# Backplane.net
KiCad netlist of a schematic drawn in EAGLE
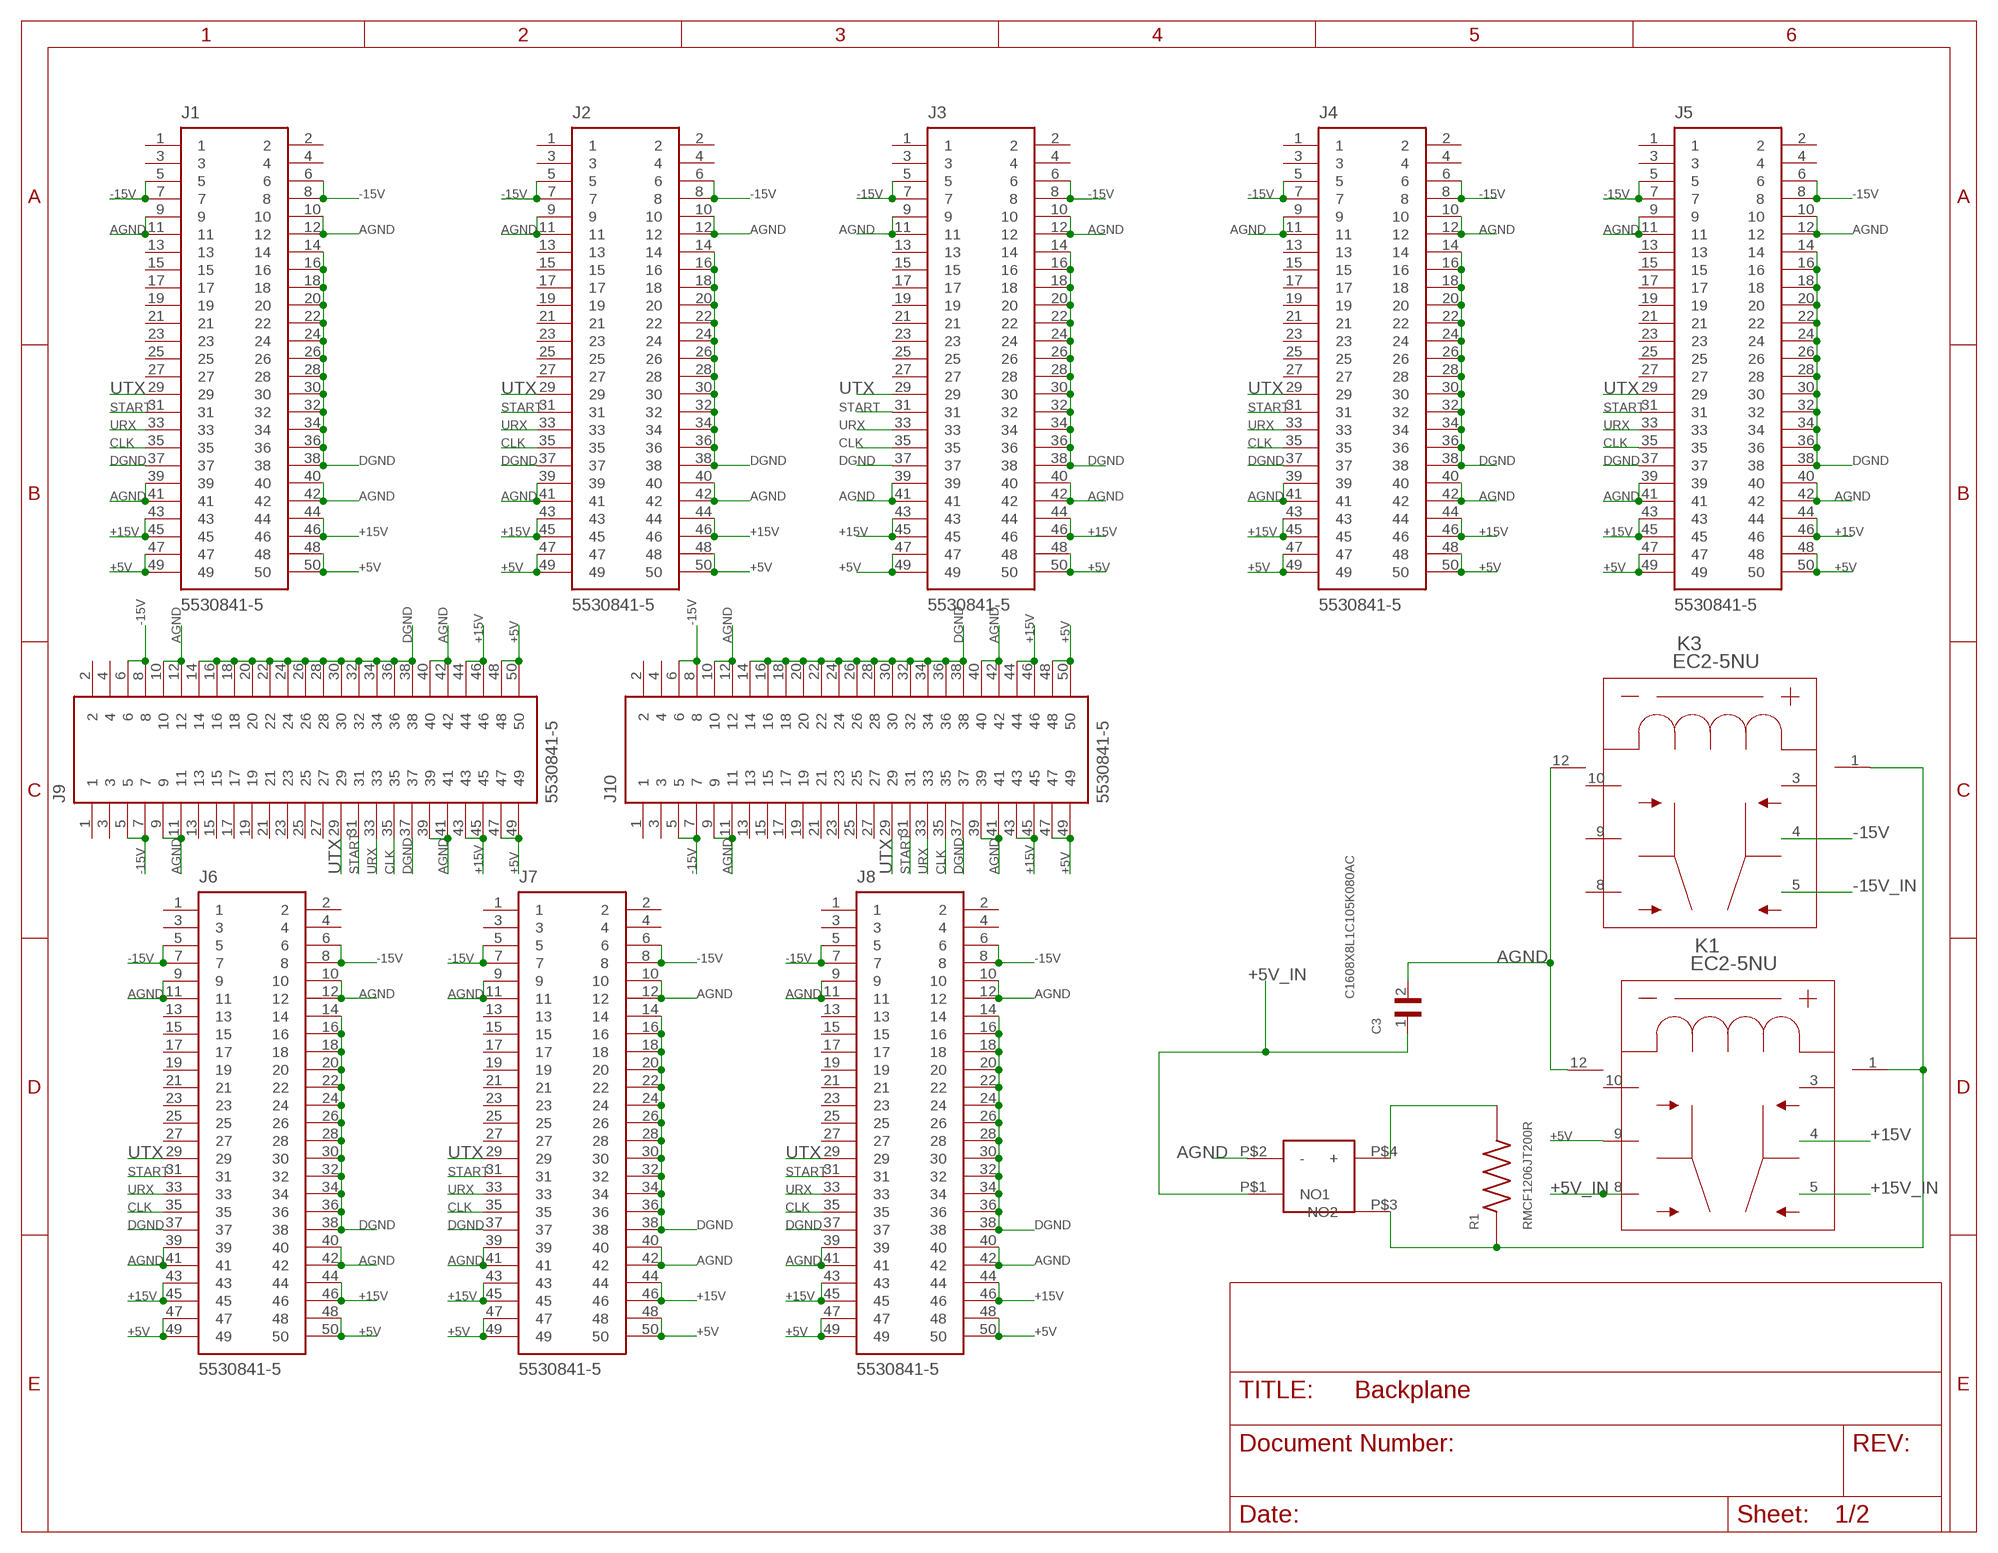
[diagram p0: schematic, sheet 1]
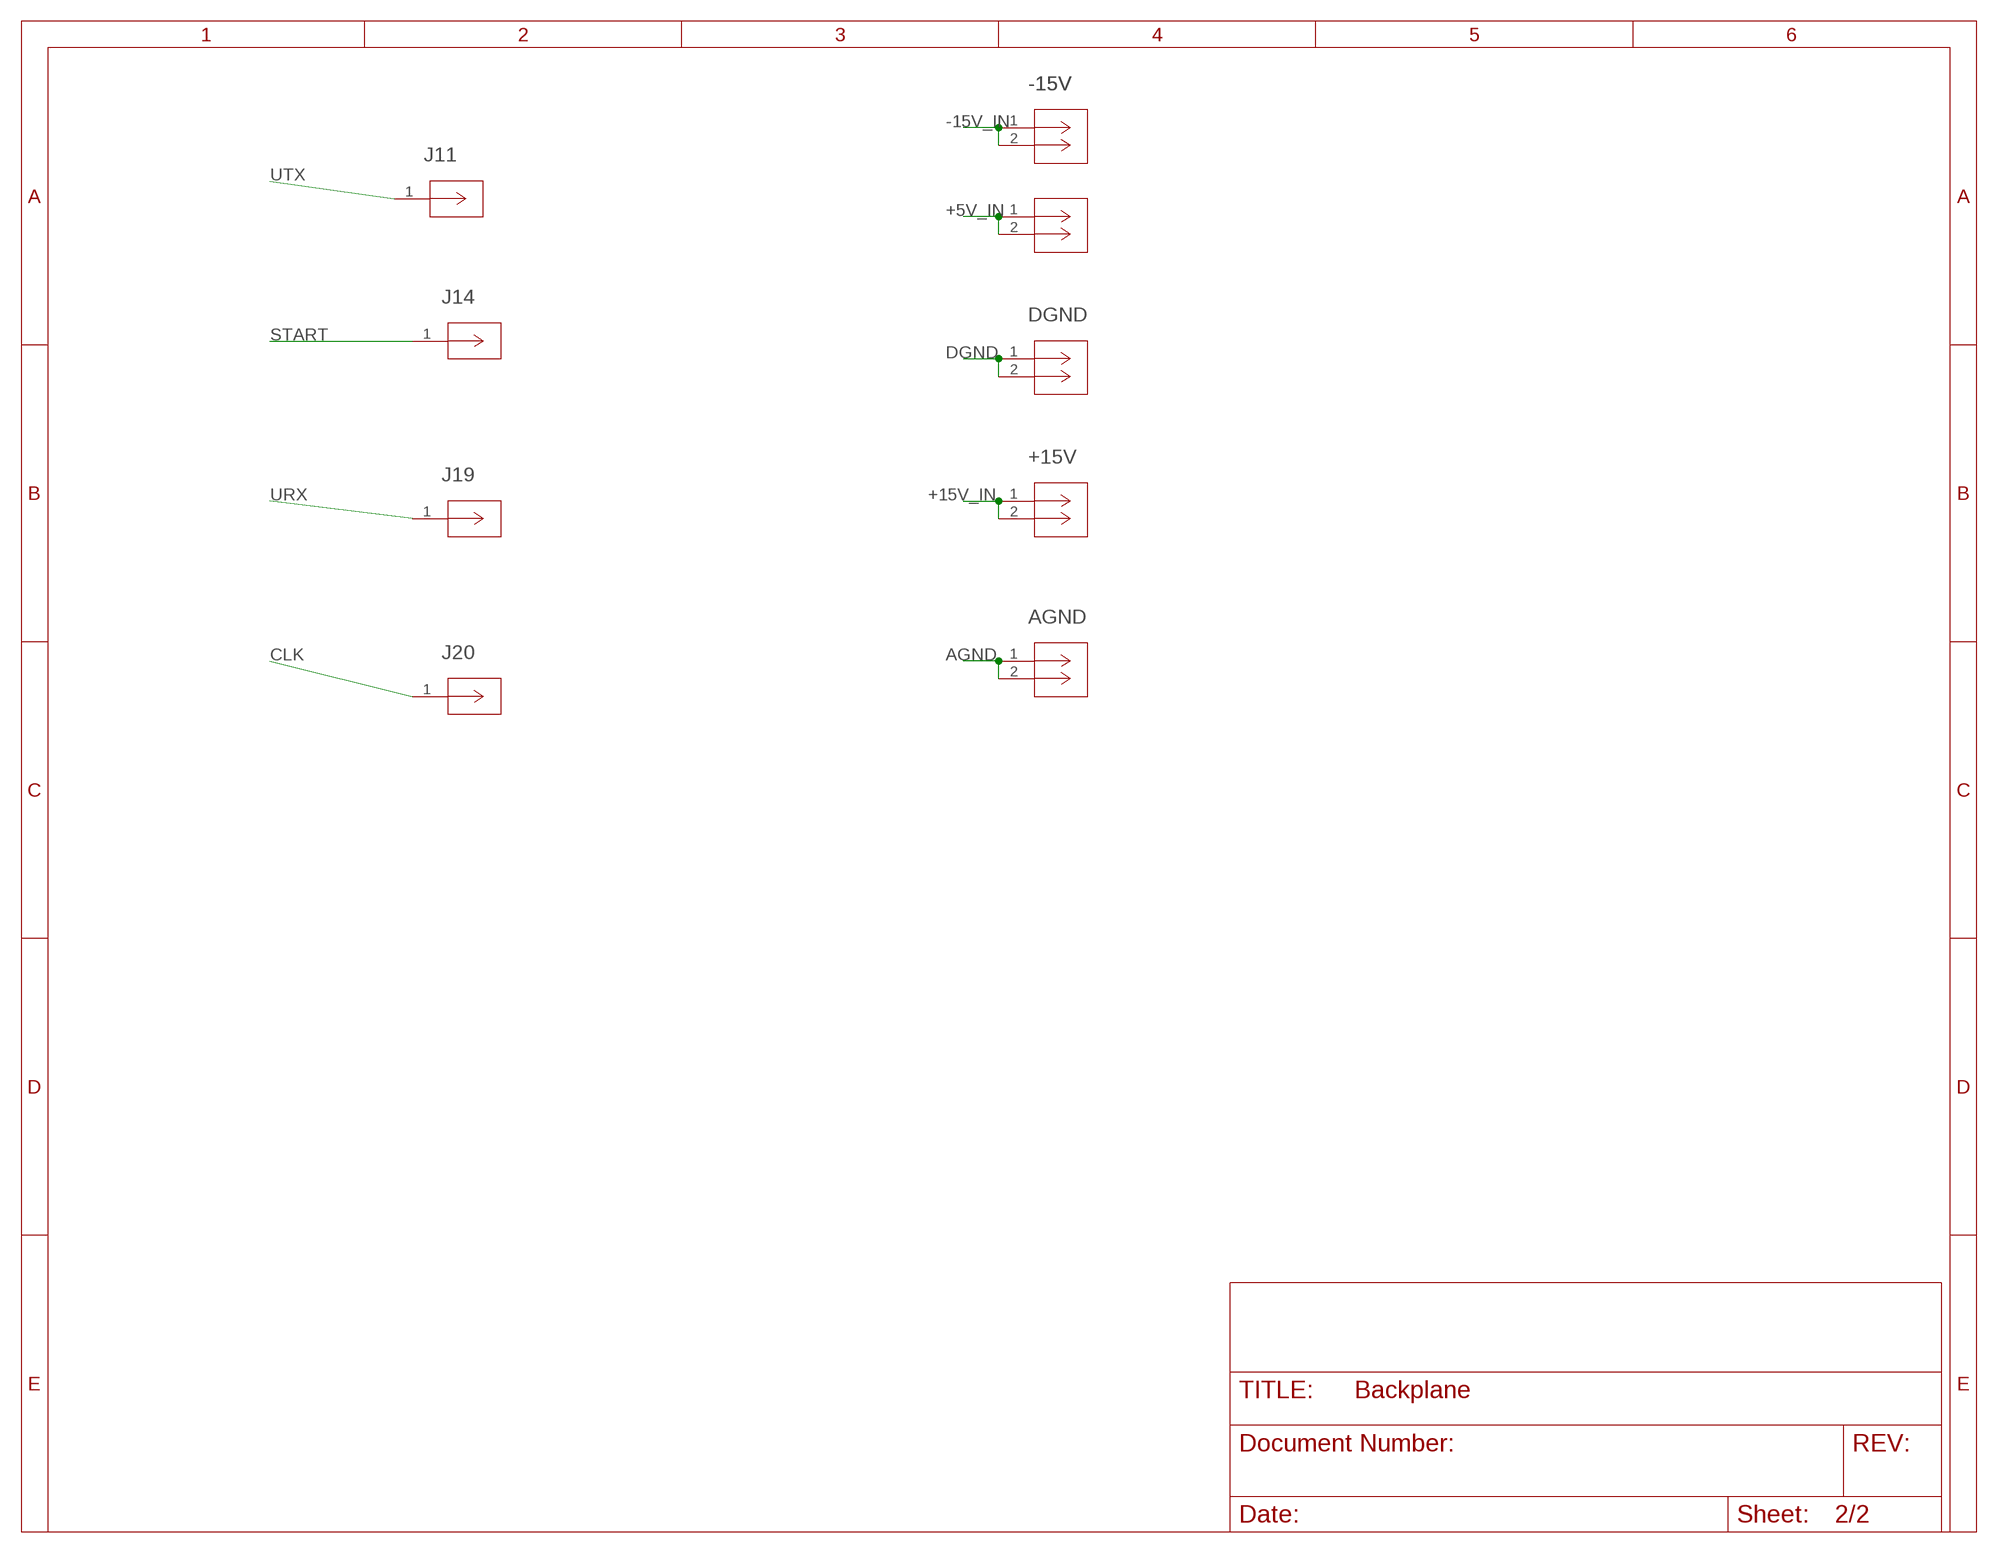
[diagram p1: schematic, sheet 2]

(export (version "E")
  (design (tool "Eeschema 10.0.6"))
  (components
    (comp (ref "C3")
      (value "C1608X8L1C105K080AC")
      (footprint "eagle-import:CAPC1608X90N")
      (fields (field (name "DIGI-KEY_PART_NUMBER") "445-175407-1-ND") (field (name "MF") "TDK"))
      (libsource (lib "eagle-import") (part "C1608X8L1C105K080AC"))
    )
    (comp (ref "J1")
      (value "5530841-5")
      (footprint "eagle-import:TE_5530841-5")
      (fields (field (name "DIGI-KEY_PART_NUMBER") "5530841-5-ND") (field (name "MF") "TE Connectivity"))
      (libsource (lib "eagle-import") (part "5530841-5"))
    )
    (comp (ref "J2")
      (value "5530841-5")
      (footprint "eagle-import:TE_5530841-5")
      (fields (field (name "DIGI-KEY_PART_NUMBER") "5530841-5-ND") (field (name "MF") "TE Connectivity"))
      (libsource (lib "eagle-import") (part "5530841-5"))
    )
    (comp (ref "J3")
      (value "5530841-5")
      (footprint "eagle-import:TE_5530841-5")
      (fields (field (name "DIGI-KEY_PART_NUMBER") "5530841-5-ND") (field (name "MF") "TE Connectivity"))
      (libsource (lib "eagle-import") (part "5530841-5"))
    )
    (comp (ref "J4")
      (value "5530841-5")
      (footprint "eagle-import:TE_5530841-5")
      (fields (field (name "DIGI-KEY_PART_NUMBER") "5530841-5-ND") (field (name "MF") "TE Connectivity"))
      (libsource (lib "eagle-import") (part "5530841-5"))
    )
    (comp (ref "J5")
      (value "5530841-5")
      (footprint "eagle-import:TE_5530841-5")
      (fields (field (name "DIGI-KEY_PART_NUMBER") "5530841-5-ND") (field (name "MF") "TE Connectivity"))
      (libsource (lib "eagle-import") (part "5530841-5"))
    )
    (comp (ref "J6")
      (value "5530841-5")
      (footprint "eagle-import:TE_5530841-5")
      (fields (field (name "DIGI-KEY_PART_NUMBER") "5530841-5-ND") (field (name "MF") "TE Connectivity"))
      (libsource (lib "eagle-import") (part "5530841-5"))
    )
    (comp (ref "J7")
      (value "5530841-5")
      (footprint "eagle-import:TE_5530841-5")
      (fields (field (name "DIGI-KEY_PART_NUMBER") "5530841-5-ND") (field (name "MF") "TE Connectivity"))
      (libsource (lib "eagle-import") (part "5530841-5"))
    )
    (comp (ref "J8")
      (value "5530841-5")
      (footprint "eagle-import:TE_5530841-5")
      (fields (field (name "DIGI-KEY_PART_NUMBER") "5530841-5-ND") (field (name "MF") "TE Connectivity"))
      (libsource (lib "eagle-import") (part "5530841-5"))
    )
    (comp (ref "J9")
      (value "5530841-5")
      (footprint "eagle-import:TE_5530841-5")
      (fields (field (name "DIGI-KEY_PART_NUMBER") "5530841-5-ND") (field (name "MF") "TE Connectivity"))
      (libsource (lib "eagle-import") (part "5530841-5"))
    )
    (comp (ref "J10")
      (value "5530841-5")
      (footprint "eagle-import:TE_5530841-5")
      (fields (field (name "DIGI-KEY_PART_NUMBER") "5530841-5-ND") (field (name "MF") "TE Connectivity"))
      (libsource (lib "eagle-import") (part "5530841-5"))
    )
    (comp (ref "K1")
      (value "EC2-5NU")
      (footprint "eagle-import:EC2NU")
      (fields (field (name "MANUFACTURER_PART_NUMBER") "EC25NU"))
      (libsource (lib "eagle-import") (part "EC2-5NU"))
    )
    (comp (ref "K3")
      (value "EC2-5NU")
      (footprint "eagle-import:EC2NU")
      (fields (field (name "MANUFACTURER_PART_NUMBER") "EC25NU"))
      (libsource (lib "eagle-import") (part "EC2-5NU"))
    )
    (comp (ref "R1")
      (value "RMCF1206JT200R")
      (footprint "eagle-import:RESC3216X70N")
      (fields
        (field (name "DIGI-KEY_PART_NUMBER") "RMCF1206JT200RCT-ND")
        (field (name "MF") "Stackpole Electronics Inc")
      )
      (libsource (lib "eagle-import") (part "RMCF1206JT200R"))
    )
    (comp (ref "U$1")
      (value "BUTTON_DEV")
      (footprint "eagle-import:BUTTON_FOOT")
      (libsource (lib "eagle-import") (part "BUTTON_DEV"))
    )
    (comp (ref "+5V")
      (value "24.243.1")
      (footprint "eagle-import:CONN_24.243_MTC")
      (fields (field (name "COPYRIGHT") "Copyright (C) 2022 Ultra Librarian. All rights reserved."))
      (libsource (lib "eagle-import") (part "24.243.1"))
    )
    (comp (ref "+15V")
      (value "24.243.1")
      (footprint "eagle-import:CONN_24.243_MTC")
      (fields (field (name "COPYRIGHT") "Copyright (C) 2018 Accelerated Designs. All rights reserved"))
      (libsource (lib "eagle-import") (part "Banana_connector_24.243.1_24.243.1"))
    )
    (comp (ref "-15V")
      (value "24.243.1")
      (footprint "eagle-import:CONN_24.243_MTC")
      (fields (field (name "COPYRIGHT") "Copyright (C) 2022 Ultra Librarian. All rights reserved."))
      (libsource (lib "eagle-import") (part "24.243.1"))
    )
    (comp (ref "AGND")
      (value "24.243.1")
      (footprint "eagle-import:CONN_24.243_MTC")
      (fields (field (name "COPYRIGHT") "Copyright (C) 2018 Accelerated Designs. All rights reserved"))
      (libsource (lib "eagle-import") (part "Banana_connector_24.243.1_24.243.1"))
    )
    (comp (ref "DGND")
      (value "24.243.1")
      (footprint "eagle-import:CONN_24.243_MTC")
      (fields (field (name "COPYRIGHT") "Copyright (C) 2018 Accelerated Designs. All rights reserved"))
      (libsource (lib "eagle-import") (part "Banana_connector_24.243.1_24.243.1"))
    )
    (comp (ref "J11")
      (value "112404")
      (footprint "eagle-import:CONN_112404_AMP")
      (fields (field (name "COPYRIGHT") "Copyright (C) 2022 Ultra Librarian. All rights reserved."))
      (libsource (lib "eagle-import") (part "112404"))
    )
    (comp (ref "J14")
      (value "112404")
      (footprint "eagle-import:CONN_112404_AMP")
      (fields (field (name "COPYRIGHT") "Copyright (C) 2022 Ultra Librarian. All rights reserved."))
      (libsource (lib "eagle-import") (part "112404"))
    )
    (comp (ref "J19")
      (value "112404")
      (footprint "eagle-import:CONN_112404_AMP")
      (fields (field (name "COPYRIGHT") "Copyright (C) 2022 Ultra Librarian. All rights reserved."))
      (libsource (lib "eagle-import") (part "112404"))
    )
    (comp (ref "J20")
      (value "112404")
      (footprint "eagle-import:CONN_112404_AMP")
      (fields (field (name "COPYRIGHT") "Copyright (C) 2022 Ultra Librarian. All rights reserved."))
      (libsource (lib "eagle-import") (part "112404"))
    )
  )
  (nets
    (net (code "1") (name "+5V") (class "Default")
      (node (ref "J1") (pin "47") (pinfunction "47_47") (pintype "passive"))
      (node (ref "J1") (pin "48") (pinfunction "48_48") (pintype "passive"))
      (node (ref "J1") (pin "49") (pinfunction "49_49") (pintype "passive"))
      (node (ref "J1") (pin "50") (pinfunction "50_50") (pintype "passive"))
      (node (ref "J10") (pin "47") (pinfunction "47_47") (pintype "passive"))
      (node (ref "J10") (pin "48") (pinfunction "48_48") (pintype "passive"))
      (node (ref "J10") (pin "49") (pinfunction "49_49") (pintype "passive"))
      (node (ref "J10") (pin "50") (pinfunction "50_50") (pintype "passive"))
      (node (ref "J2") (pin "47") (pinfunction "47_47") (pintype "passive"))
      (node (ref "J2") (pin "48") (pinfunction "48_48") (pintype "passive"))
      (node (ref "J2") (pin "49") (pinfunction "49_49") (pintype "passive"))
      (node (ref "J2") (pin "50") (pinfunction "50_50") (pintype "passive"))
      (node (ref "J3") (pin "47") (pinfunction "47_47") (pintype "passive"))
      (node (ref "J3") (pin "48") (pinfunction "48_48") (pintype "passive"))
      (node (ref "J3") (pin "49") (pinfunction "49_49") (pintype "passive"))
      (node (ref "J3") (pin "50") (pinfunction "50_50") (pintype "passive"))
      (node (ref "J4") (pin "47") (pinfunction "47_47") (pintype "passive"))
      (node (ref "J4") (pin "48") (pinfunction "48_48") (pintype "passive"))
      (node (ref "J4") (pin "49") (pinfunction "49_49") (pintype "passive"))
      (node (ref "J4") (pin "50") (pinfunction "50_50") (pintype "passive"))
      (node (ref "J5") (pin "47") (pinfunction "47_47") (pintype "passive"))
      (node (ref "J5") (pin "48") (pinfunction "48_48") (pintype "passive"))
      (node (ref "J5") (pin "49") (pinfunction "49_49") (pintype "passive"))
      (node (ref "J5") (pin "50") (pinfunction "50_50") (pintype "passive"))
      (node (ref "J6") (pin "47") (pinfunction "47_47") (pintype "passive"))
      (node (ref "J6") (pin "48") (pinfunction "48_48") (pintype "passive"))
      (node (ref "J6") (pin "49") (pinfunction "49_49") (pintype "passive"))
      (node (ref "J6") (pin "50") (pinfunction "50_50") (pintype "passive"))
      (node (ref "J7") (pin "47") (pinfunction "47_47") (pintype "passive"))
      (node (ref "J7") (pin "48") (pinfunction "48_48") (pintype "passive"))
      (node (ref "J7") (pin "49") (pinfunction "49_49") (pintype "passive"))
      (node (ref "J7") (pin "50") (pinfunction "50_50") (pintype "passive"))
      (node (ref "J8") (pin "47") (pinfunction "47_47") (pintype "passive"))
      (node (ref "J8") (pin "48") (pinfunction "48_48") (pintype "passive"))
      (node (ref "J8") (pin "49") (pinfunction "49_49") (pintype "passive"))
      (node (ref "J8") (pin "50") (pinfunction "50_50") (pintype "passive"))
      (node (ref "J9") (pin "47") (pinfunction "47_47") (pintype "passive"))
      (node (ref "J9") (pin "48") (pinfunction "48_48") (pintype "passive"))
      (node (ref "J9") (pin "49") (pinfunction "49_49") (pintype "passive"))
      (node (ref "J9") (pin "50") (pinfunction "50_50") (pintype "passive"))
      (node (ref "K1") (pin "9") (pinfunction "6_9") (pintype "passive"))
    )
    (net (code "2") (name "+5V_IN") (class "Default")
      (node (ref "+5V") (pin "1") (pinfunction "1_1") (pintype "passive"))
      (node (ref "+5V") (pin "2") (pinfunction "2_2") (pintype "passive"))
      (node (ref "C3") (pin "1") (pinfunction "1_1") (pintype "passive"))
      (node (ref "K1") (pin "8") (pinfunction "5_8") (pintype "passive"))
      (node (ref "U$1") (pin "P$1") (pinfunction "NO1_P$1") (pintype "bidirectional"))
    )
    (net (code "3") (name "+15V") (class "Default")
      (node (ref "J1") (pin "43") (pinfunction "43_43") (pintype "passive"))
      (node (ref "J1") (pin "44") (pinfunction "44_44") (pintype "passive"))
      (node (ref "J1") (pin "45") (pinfunction "45_45") (pintype "passive"))
      (node (ref "J1") (pin "46") (pinfunction "46_46") (pintype "passive"))
      (node (ref "J10") (pin "43") (pinfunction "43_43") (pintype "passive"))
      (node (ref "J10") (pin "44") (pinfunction "44_44") (pintype "passive"))
      (node (ref "J10") (pin "45") (pinfunction "45_45") (pintype "passive"))
      (node (ref "J10") (pin "46") (pinfunction "46_46") (pintype "passive"))
      (node (ref "J2") (pin "43") (pinfunction "43_43") (pintype "passive"))
      (node (ref "J2") (pin "44") (pinfunction "44_44") (pintype "passive"))
      (node (ref "J2") (pin "45") (pinfunction "45_45") (pintype "passive"))
      (node (ref "J2") (pin "46") (pinfunction "46_46") (pintype "passive"))
      (node (ref "J3") (pin "43") (pinfunction "43_43") (pintype "passive"))
      (node (ref "J3") (pin "44") (pinfunction "44_44") (pintype "passive"))
      (node (ref "J3") (pin "45") (pinfunction "45_45") (pintype "passive"))
      (node (ref "J3") (pin "46") (pinfunction "46_46") (pintype "passive"))
      (node (ref "J4") (pin "43") (pinfunction "43_43") (pintype "passive"))
      (node (ref "J4") (pin "44") (pinfunction "44_44") (pintype "passive"))
      (node (ref "J4") (pin "45") (pinfunction "45_45") (pintype "passive"))
      (node (ref "J4") (pin "46") (pinfunction "46_46") (pintype "passive"))
      (node (ref "J5") (pin "43") (pinfunction "43_43") (pintype "passive"))
      (node (ref "J5") (pin "44") (pinfunction "44_44") (pintype "passive"))
      (node (ref "J5") (pin "45") (pinfunction "45_45") (pintype "passive"))
      (node (ref "J5") (pin "46") (pinfunction "46_46") (pintype "passive"))
      (node (ref "J6") (pin "43") (pinfunction "43_43") (pintype "passive"))
      (node (ref "J6") (pin "44") (pinfunction "44_44") (pintype "passive"))
      (node (ref "J6") (pin "45") (pinfunction "45_45") (pintype "passive"))
      (node (ref "J6") (pin "46") (pinfunction "46_46") (pintype "passive"))
      (node (ref "J7") (pin "43") (pinfunction "43_43") (pintype "passive"))
      (node (ref "J7") (pin "44") (pinfunction "44_44") (pintype "passive"))
      (node (ref "J7") (pin "45") (pinfunction "45_45") (pintype "passive"))
      (node (ref "J7") (pin "46") (pinfunction "46_46") (pintype "passive"))
      (node (ref "J8") (pin "43") (pinfunction "43_43") (pintype "passive"))
      (node (ref "J8") (pin "44") (pinfunction "44_44") (pintype "passive"))
      (node (ref "J8") (pin "45") (pinfunction "45_45") (pintype "passive"))
      (node (ref "J8") (pin "46") (pinfunction "46_46") (pintype "passive"))
      (node (ref "J9") (pin "43") (pinfunction "43_43") (pintype "passive"))
      (node (ref "J9") (pin "44") (pinfunction "44_44") (pintype "passive"))
      (node (ref "J9") (pin "45") (pinfunction "45_45") (pintype "passive"))
      (node (ref "J9") (pin "46") (pinfunction "46_46") (pintype "passive"))
      (node (ref "K1") (pin "4") (pinfunction "3_4") (pintype "passive"))
    )
    (net (code "4") (name "+15V_IN") (class "Default")
      (node (ref "+15V") (pin "1") (pinfunction "1_1") (pintype "passive"))
      (node (ref "+15V") (pin "2") (pinfunction "2_2") (pintype "passive"))
      (node (ref "K1") (pin "5") (pinfunction "4_5") (pintype "passive"))
    )
    (net (code "5") (name "-15V") (class "Default")
      (node (ref "J1") (pin "5") (pinfunction "5_5") (pintype "passive"))
      (node (ref "J1") (pin "6") (pinfunction "6_6") (pintype "passive"))
      (node (ref "J1") (pin "7") (pinfunction "7_7") (pintype "passive"))
      (node (ref "J1") (pin "8") (pinfunction "8_8") (pintype "passive"))
      (node (ref "J10") (pin "5") (pinfunction "5_5") (pintype "passive"))
      (node (ref "J10") (pin "6") (pinfunction "6_6") (pintype "passive"))
      (node (ref "J10") (pin "7") (pinfunction "7_7") (pintype "passive"))
      (node (ref "J10") (pin "8") (pinfunction "8_8") (pintype "passive"))
      (node (ref "J2") (pin "5") (pinfunction "5_5") (pintype "passive"))
      (node (ref "J2") (pin "6") (pinfunction "6_6") (pintype "passive"))
      (node (ref "J2") (pin "7") (pinfunction "7_7") (pintype "passive"))
      (node (ref "J2") (pin "8") (pinfunction "8_8") (pintype "passive"))
      (node (ref "J3") (pin "5") (pinfunction "5_5") (pintype "passive"))
      (node (ref "J3") (pin "6") (pinfunction "6_6") (pintype "passive"))
      (node (ref "J3") (pin "7") (pinfunction "7_7") (pintype "passive"))
      (node (ref "J3") (pin "8") (pinfunction "8_8") (pintype "passive"))
      (node (ref "J4") (pin "5") (pinfunction "5_5") (pintype "passive"))
      (node (ref "J4") (pin "6") (pinfunction "6_6") (pintype "passive"))
      (node (ref "J4") (pin "7") (pinfunction "7_7") (pintype "passive"))
      (node (ref "J4") (pin "8") (pinfunction "8_8") (pintype "passive"))
      (node (ref "J5") (pin "5") (pinfunction "5_5") (pintype "passive"))
      (node (ref "J5") (pin "6") (pinfunction "6_6") (pintype "passive"))
      (node (ref "J5") (pin "7") (pinfunction "7_7") (pintype "passive"))
      (node (ref "J5") (pin "8") (pinfunction "8_8") (pintype "passive"))
      (node (ref "J6") (pin "5") (pinfunction "5_5") (pintype "passive"))
      (node (ref "J6") (pin "6") (pinfunction "6_6") (pintype "passive"))
      (node (ref "J6") (pin "7") (pinfunction "7_7") (pintype "passive"))
      (node (ref "J6") (pin "8") (pinfunction "8_8") (pintype "passive"))
      (node (ref "J7") (pin "5") (pinfunction "5_5") (pintype "passive"))
      (node (ref "J7") (pin "6") (pinfunction "6_6") (pintype "passive"))
      (node (ref "J7") (pin "7") (pinfunction "7_7") (pintype "passive"))
      (node (ref "J7") (pin "8") (pinfunction "8_8") (pintype "passive"))
      (node (ref "J8") (pin "5") (pinfunction "5_5") (pintype "passive"))
      (node (ref "J8") (pin "6") (pinfunction "6_6") (pintype "passive"))
      (node (ref "J8") (pin "7") (pinfunction "7_7") (pintype "passive"))
      (node (ref "J8") (pin "8") (pinfunction "8_8") (pintype "passive"))
      (node (ref "J9") (pin "5") (pinfunction "5_5") (pintype "passive"))
      (node (ref "J9") (pin "6") (pinfunction "6_6") (pintype "passive"))
      (node (ref "J9") (pin "7") (pinfunction "7_7") (pintype "passive"))
      (node (ref "J9") (pin "8") (pinfunction "8_8") (pintype "passive"))
      (node (ref "K3") (pin "4") (pinfunction "3_4") (pintype "passive"))
    )
    (net (code "6") (name "-15V_IN") (class "Default")
      (node (ref "-15V") (pin "1") (pinfunction "1_1") (pintype "passive"))
      (node (ref "-15V") (pin "2") (pinfunction "2_2") (pintype "passive"))
      (node (ref "K3") (pin "5") (pinfunction "4_5") (pintype "passive"))
    )
    (net (code "7") (name "AGND") (class "Default")
      (node (ref "AGND") (pin "1") (pinfunction "1_1") (pintype "passive"))
      (node (ref "AGND") (pin "2") (pinfunction "2_2") (pintype "passive"))
      (node (ref "C3") (pin "2") (pinfunction "2_2") (pintype "passive"))
      (node (ref "J1") (pin "10") (pinfunction "10_10") (pintype "passive"))
      (node (ref "J1") (pin "11") (pinfunction "11_11") (pintype "passive"))
      (node (ref "J1") (pin "12") (pinfunction "12_12") (pintype "passive"))
      (node (ref "J1") (pin "39") (pinfunction "39_39") (pintype "passive"))
      (node (ref "J1") (pin "40") (pinfunction "40_40") (pintype "passive"))
      (node (ref "J1") (pin "41") (pinfunction "41_41") (pintype "passive"))
      (node (ref "J1") (pin "42") (pinfunction "42_42") (pintype "passive"))
      (node (ref "J1") (pin "9") (pinfunction "9_9") (pintype "passive"))
      (node (ref "J10") (pin "10") (pinfunction "10_10") (pintype "passive"))
      (node (ref "J10") (pin "11") (pinfunction "11_11") (pintype "passive"))
      (node (ref "J10") (pin "12") (pinfunction "12_12") (pintype "passive"))
      (node (ref "J10") (pin "39") (pinfunction "39_39") (pintype "passive"))
      (node (ref "J10") (pin "40") (pinfunction "40_40") (pintype "passive"))
      (node (ref "J10") (pin "41") (pinfunction "41_41") (pintype "passive"))
      (node (ref "J10") (pin "42") (pinfunction "42_42") (pintype "passive"))
      (node (ref "J10") (pin "9") (pinfunction "9_9") (pintype "passive"))
      (node (ref "J2") (pin "10") (pinfunction "10_10") (pintype "passive"))
      (node (ref "J2") (pin "11") (pinfunction "11_11") (pintype "passive"))
      (node (ref "J2") (pin "12") (pinfunction "12_12") (pintype "passive"))
      (node (ref "J2") (pin "39") (pinfunction "39_39") (pintype "passive"))
      (node (ref "J2") (pin "40") (pinfunction "40_40") (pintype "passive"))
      (node (ref "J2") (pin "41") (pinfunction "41_41") (pintype "passive"))
      (node (ref "J2") (pin "42") (pinfunction "42_42") (pintype "passive"))
      (node (ref "J2") (pin "9") (pinfunction "9_9") (pintype "passive"))
      (node (ref "J3") (pin "10") (pinfunction "10_10") (pintype "passive"))
      (node (ref "J3") (pin "11") (pinfunction "11_11") (pintype "passive"))
      (node (ref "J3") (pin "12") (pinfunction "12_12") (pintype "passive"))
      (node (ref "J3") (pin "39") (pinfunction "39_39") (pintype "passive"))
      (node (ref "J3") (pin "40") (pinfunction "40_40") (pintype "passive"))
      (node (ref "J3") (pin "41") (pinfunction "41_41") (pintype "passive"))
      (node (ref "J3") (pin "42") (pinfunction "42_42") (pintype "passive"))
      (node (ref "J3") (pin "9") (pinfunction "9_9") (pintype "passive"))
      (node (ref "J4") (pin "10") (pinfunction "10_10") (pintype "passive"))
      (node (ref "J4") (pin "11") (pinfunction "11_11") (pintype "passive"))
      (node (ref "J4") (pin "12") (pinfunction "12_12") (pintype "passive"))
      (node (ref "J4") (pin "39") (pinfunction "39_39") (pintype "passive"))
      (node (ref "J4") (pin "40") (pinfunction "40_40") (pintype "passive"))
      (node (ref "J4") (pin "41") (pinfunction "41_41") (pintype "passive"))
      (node (ref "J4") (pin "42") (pinfunction "42_42") (pintype "passive"))
      (node (ref "J4") (pin "9") (pinfunction "9_9") (pintype "passive"))
      (node (ref "J5") (pin "10") (pinfunction "10_10") (pintype "passive"))
      (node (ref "J5") (pin "11") (pinfunction "11_11") (pintype "passive"))
      (node (ref "J5") (pin "12") (pinfunction "12_12") (pintype "passive"))
      (node (ref "J5") (pin "39") (pinfunction "39_39") (pintype "passive"))
      (node (ref "J5") (pin "40") (pinfunction "40_40") (pintype "passive"))
      (node (ref "J5") (pin "41") (pinfunction "41_41") (pintype "passive"))
      (node (ref "J5") (pin "42") (pinfunction "42_42") (pintype "passive"))
      (node (ref "J5") (pin "9") (pinfunction "9_9") (pintype "passive"))
      (node (ref "J6") (pin "10") (pinfunction "10_10") (pintype "passive"))
      (node (ref "J6") (pin "11") (pinfunction "11_11") (pintype "passive"))
      (node (ref "J6") (pin "12") (pinfunction "12_12") (pintype "passive"))
      (node (ref "J6") (pin "39") (pinfunction "39_39") (pintype "passive"))
      (node (ref "J6") (pin "40") (pinfunction "40_40") (pintype "passive"))
      (node (ref "J6") (pin "41") (pinfunction "41_41") (pintype "passive"))
      (node (ref "J6") (pin "42") (pinfunction "42_42") (pintype "passive"))
      (node (ref "J6") (pin "9") (pinfunction "9_9") (pintype "passive"))
      (node (ref "J7") (pin "10") (pinfunction "10_10") (pintype "passive"))
      (node (ref "J7") (pin "11") (pinfunction "11_11") (pintype "passive"))
      (node (ref "J7") (pin "12") (pinfunction "12_12") (pintype "passive"))
      (node (ref "J7") (pin "39") (pinfunction "39_39") (pintype "passive"))
      (node (ref "J7") (pin "40") (pinfunction "40_40") (pintype "passive"))
      (node (ref "J7") (pin "41") (pinfunction "41_41") (pintype "passive"))
      (node (ref "J7") (pin "42") (pinfunction "42_42") (pintype "passive"))
      (node (ref "J7") (pin "9") (pinfunction "9_9") (pintype "passive"))
      (node (ref "J8") (pin "10") (pinfunction "10_10") (pintype "passive"))
      (node (ref "J8") (pin "11") (pinfunction "11_11") (pintype "passive"))
      (node (ref "J8") (pin "12") (pinfunction "12_12") (pintype "passive"))
      (node (ref "J8") (pin "39") (pinfunction "39_39") (pintype "passive"))
      (node (ref "J8") (pin "40") (pinfunction "40_40") (pintype "passive"))
      (node (ref "J8") (pin "41") (pinfunction "41_41") (pintype "passive"))
      (node (ref "J8") (pin "42") (pinfunction "42_42") (pintype "passive"))
      (node (ref "J8") (pin "9") (pinfunction "9_9") (pintype "passive"))
      (node (ref "J9") (pin "10") (pinfunction "10_10") (pintype "passive"))
      (node (ref "J9") (pin "11") (pinfunction "11_11") (pintype "passive"))
      (node (ref "J9") (pin "12") (pinfunction "12_12") (pintype "passive"))
      (node (ref "J9") (pin "39") (pinfunction "39_39") (pintype "passive"))
      (node (ref "J9") (pin "40") (pinfunction "40_40") (pintype "passive"))
      (node (ref "J9") (pin "41") (pinfunction "41_41") (pintype "passive"))
      (node (ref "J9") (pin "42") (pinfunction "42_42") (pintype "passive"))
      (node (ref "J9") (pin "9") (pinfunction "9_9") (pintype "passive"))
      (node (ref "K1") (pin "12") (pinfunction "8_12") (pintype "passive"))
      (node (ref "K3") (pin "12") (pinfunction "8_12") (pintype "passive"))
      (node (ref "U$1") (pin "P$2") (pinfunction "-_P$2") (pintype "bidirectional"))
    )
    (net (code "8") (name "CLK") (class "Default")
      (node (ref "J1") (pin "35") (pinfunction "35_35") (pintype "passive"))
      (node (ref "J10") (pin "35") (pinfunction "35_35") (pintype "passive"))
      (node (ref "J2") (pin "35") (pinfunction "35_35") (pintype "passive"))
      (node (ref "J20") (pin "1") (pinfunction "1_1") (pintype "passive"))
      (node (ref "J3") (pin "35") (pinfunction "35_35") (pintype "passive"))
      (node (ref "J4") (pin "35") (pinfunction "35_35") (pintype "passive"))
      (node (ref "J5") (pin "35") (pinfunction "35_35") (pintype "passive"))
      (node (ref "J6") (pin "35") (pinfunction "35_35") (pintype "passive"))
      (node (ref "J7") (pin "35") (pinfunction "35_35") (pintype "passive"))
      (node (ref "J8") (pin "35") (pinfunction "35_35") (pintype "passive"))
      (node (ref "J9") (pin "35") (pinfunction "35_35") (pintype "passive"))
    )
    (net (code "9") (name "DGND") (class "Default")
      (node (ref "DGND") (pin "1") (pinfunction "1_1") (pintype "passive"))
      (node (ref "DGND") (pin "2") (pinfunction "2_2") (pintype "passive"))
      (node (ref "J1") (pin "14") (pinfunction "14_14") (pintype "passive"))
      (node (ref "J1") (pin "16") (pinfunction "16_16") (pintype "passive"))
      (node (ref "J1") (pin "18") (pinfunction "18_18") (pintype "passive"))
      (node (ref "J1") (pin "20") (pinfunction "20_20") (pintype "passive"))
      (node (ref "J1") (pin "22") (pinfunction "22_22") (pintype "passive"))
      (node (ref "J1") (pin "24") (pinfunction "24_24") (pintype "passive"))
      (node (ref "J1") (pin "26") (pinfunction "26_26") (pintype "passive"))
      (node (ref "J1") (pin "28") (pinfunction "28_28") (pintype "passive"))
      (node (ref "J1") (pin "30") (pinfunction "30_30") (pintype "passive"))
      (node (ref "J1") (pin "32") (pinfunction "32_32") (pintype "passive"))
      (node (ref "J1") (pin "34") (pinfunction "34_34") (pintype "passive"))
      (node (ref "J1") (pin "36") (pinfunction "36_36") (pintype "passive"))
      (node (ref "J1") (pin "37") (pinfunction "37_37") (pintype "passive"))
      (node (ref "J1") (pin "38") (pinfunction "38_38") (pintype "passive"))
      (node (ref "J10") (pin "14") (pinfunction "14_14") (pintype "passive"))
      (node (ref "J10") (pin "16") (pinfunction "16_16") (pintype "passive"))
      (node (ref "J10") (pin "18") (pinfunction "18_18") (pintype "passive"))
      (node (ref "J10") (pin "20") (pinfunction "20_20") (pintype "passive"))
      (node (ref "J10") (pin "22") (pinfunction "22_22") (pintype "passive"))
      (node (ref "J10") (pin "24") (pinfunction "24_24") (pintype "passive"))
      (node (ref "J10") (pin "26") (pinfunction "26_26") (pintype "passive"))
      (node (ref "J10") (pin "28") (pinfunction "28_28") (pintype "passive"))
      (node (ref "J10") (pin "30") (pinfunction "30_30") (pintype "passive"))
      (node (ref "J10") (pin "32") (pinfunction "32_32") (pintype "passive"))
      (node (ref "J10") (pin "34") (pinfunction "34_34") (pintype "passive"))
      (node (ref "J10") (pin "36") (pinfunction "36_36") (pintype "passive"))
      (node (ref "J10") (pin "37") (pinfunction "37_37") (pintype "passive"))
      (node (ref "J10") (pin "38") (pinfunction "38_38") (pintype "passive"))
      (node (ref "J2") (pin "14") (pinfunction "14_14") (pintype "passive"))
      (node (ref "J2") (pin "16") (pinfunction "16_16") (pintype "passive"))
      (node (ref "J2") (pin "18") (pinfunction "18_18") (pintype "passive"))
      (node (ref "J2") (pin "20") (pinfunction "20_20") (pintype "passive"))
      (node (ref "J2") (pin "22") (pinfunction "22_22") (pintype "passive"))
      (node (ref "J2") (pin "24") (pinfunction "24_24") (pintype "passive"))
      (node (ref "J2") (pin "26") (pinfunction "26_26") (pintype "passive"))
      (node (ref "J2") (pin "28") (pinfunction "28_28") (pintype "passive"))
      (node (ref "J2") (pin "30") (pinfunction "30_30") (pintype "passive"))
      (node (ref "J2") (pin "32") (pinfunction "32_32") (pintype "passive"))
      (node (ref "J2") (pin "34") (pinfunction "34_34") (pintype "passive"))
      (node (ref "J2") (pin "36") (pinfunction "36_36") (pintype "passive"))
      (node (ref "J2") (pin "37") (pinfunction "37_37") (pintype "passive"))
      (node (ref "J2") (pin "38") (pinfunction "38_38") (pintype "passive"))
      (node (ref "J3") (pin "14") (pinfunction "14_14") (pintype "passive"))
      (node (ref "J3") (pin "16") (pinfunction "16_16") (pintype "passive"))
      (node (ref "J3") (pin "18") (pinfunction "18_18") (pintype "passive"))
      (node (ref "J3") (pin "20") (pinfunction "20_20") (pintype "passive"))
      (node (ref "J3") (pin "22") (pinfunction "22_22") (pintype "passive"))
      (node (ref "J3") (pin "24") (pinfunction "24_24") (pintype "passive"))
      (node (ref "J3") (pin "26") (pinfunction "26_26") (pintype "passive"))
      (node (ref "J3") (pin "28") (pinfunction "28_28") (pintype "passive"))
      (node (ref "J3") (pin "30") (pinfunction "30_30") (pintype "passive"))
      (node (ref "J3") (pin "32") (pinfunction "32_32") (pintype "passive"))
      (node (ref "J3") (pin "34") (pinfunction "34_34") (pintype "passive"))
      (node (ref "J3") (pin "36") (pinfunction "36_36") (pintype "passive"))
      (node (ref "J3") (pin "37") (pinfunction "37_37") (pintype "passive"))
      (node (ref "J3") (pin "38") (pinfunction "38_38") (pintype "passive"))
      (node (ref "J4") (pin "14") (pinfunction "14_14") (pintype "passive"))
      (node (ref "J4") (pin "16") (pinfunction "16_16") (pintype "passive"))
      (node (ref "J4") (pin "18") (pinfunction "18_18") (pintype "passive"))
      (node (ref "J4") (pin "20") (pinfunction "20_20") (pintype "passive"))
      (node (ref "J4") (pin "22") (pinfunction "22_22") (pintype "passive"))
      (node (ref "J4") (pin "24") (pinfunction "24_24") (pintype "passive"))
      (node (ref "J4") (pin "26") (pinfunction "26_26") (pintype "passive"))
      (node (ref "J4") (pin "28") (pinfunction "28_28") (pintype "passive"))
      (node (ref "J4") (pin "30") (pinfunction "30_30") (pintype "passive"))
      (node (ref "J4") (pin "32") (pinfunction "32_32") (pintype "passive"))
      (node (ref "J4") (pin "34") (pinfunction "34_34") (pintype "passive"))
      (node (ref "J4") (pin "36") (pinfunction "36_36") (pintype "passive"))
      (node (ref "J4") (pin "37") (pinfunction "37_37") (pintype "passive"))
      (node (ref "J4") (pin "38") (pinfunction "38_38") (pintype "passive"))
      (node (ref "J5") (pin "14") (pinfunction "14_14") (pintype "passive"))
      (node (ref "J5") (pin "16") (pinfunction "16_16") (pintype "passive"))
      (node (ref "J5") (pin "18") (pinfunction "18_18") (pintype "passive"))
      (node (ref "J5") (pin "20") (pinfunction "20_20") (pintype "passive"))
      (node (ref "J5") (pin "22") (pinfunction "22_22") (pintype "passive"))
      (node (ref "J5") (pin "24") (pinfunction "24_24") (pintype "passive"))
      (node (ref "J5") (pin "26") (pinfunction "26_26") (pintype "passive"))
      (node (ref "J5") (pin "28") (pinfunction "28_28") (pintype "passive"))
      (node (ref "J5") (pin "30") (pinfunction "30_30") (pintype "passive"))
      (node (ref "J5") (pin "32") (pinfunction "32_32") (pintype "passive"))
      (node (ref "J5") (pin "34") (pinfunction "34_34") (pintype "passive"))
      (node (ref "J5") (pin "36") (pinfunction "36_36") (pintype "passive"))
      (node (ref "J5") (pin "37") (pinfunction "37_37") (pintype "passive"))
      (node (ref "J5") (pin "38") (pinfunction "38_38") (pintype "passive"))
      (node (ref "J6") (pin "14") (pinfunction "14_14") (pintype "passive"))
      (node (ref "J6") (pin "16") (pinfunction "16_16") (pintype "passive"))
      (node (ref "J6") (pin "18") (pinfunction "18_18") (pintype "passive"))
      (node (ref "J6") (pin "20") (pinfunction "20_20") (pintype "passive"))
      (node (ref "J6") (pin "22") (pinfunction "22_22") (pintype "passive"))
      (node (ref "J6") (pin "24") (pinfunction "24_24") (pintype "passive"))
      (node (ref "J6") (pin "26") (pinfunction "26_26") (pintype "passive"))
      (node (ref "J6") (pin "28") (pinfunction "28_28") (pintype "passive"))
      (node (ref "J6") (pin "30") (pinfunction "30_30") (pintype "passive"))
      (node (ref "J6") (pin "32") (pinfunction "32_32") (pintype "passive"))
      (node (ref "J6") (pin "34") (pinfunction "34_34") (pintype "passive"))
      (node (ref "J6") (pin "36") (pinfunction "36_36") (pintype "passive"))
      (node (ref "J6") (pin "37") (pinfunction "37_37") (pintype "passive"))
      (node (ref "J6") (pin "38") (pinfunction "38_38") (pintype "passive"))
      (node (ref "J7") (pin "14") (pinfunction "14_14") (pintype "passive"))
      (node (ref "J7") (pin "16") (pinfunction "16_16") (pintype "passive"))
      (node (ref "J7") (pin "18") (pinfunction "18_18") (pintype "passive"))
      (node (ref "J7") (pin "20") (pinfunction "20_20") (pintype "passive"))
      (node (ref "J7") (pin "22") (pinfunction "22_22") (pintype "passive"))
      (node (ref "J7") (pin "24") (pinfunction "24_24") (pintype "passive"))
      (node (ref "J7") (pin "26") (pinfunction "26_26") (pintype "passive"))
      (node (ref "J7") (pin "28") (pinfunction "28_28") (pintype "passive"))
      (node (ref "J7") (pin "30") (pinfunction "30_30") (pintype "passive"))
      (node (ref "J7") (pin "32") (pinfunction "32_32") (pintype "passive"))
      (node (ref "J7") (pin "34") (pinfunction "34_34") (pintype "passive"))
      (node (ref "J7") (pin "36") (pinfunction "36_36") (pintype "passive"))
      (node (ref "J7") (pin "37") (pinfunction "37_37") (pintype "passive"))
      (node (ref "J7") (pin "38") (pinfunction "38_38") (pintype "passive"))
      (node (ref "J8") (pin "14") (pinfunction "14_14") (pintype "passive"))
      (node (ref "J8") (pin "16") (pinfunction "16_16") (pintype "passive"))
      (node (ref "J8") (pin "18") (pinfunction "18_18") (pintype "passive"))
      (node (ref "J8") (pin "20") (pinfunction "20_20") (pintype "passive"))
      (node (ref "J8") (pin "22") (pinfunction "22_22") (pintype "passive"))
      (node (ref "J8") (pin "24") (pinfunction "24_24") (pintype "passive"))
      (node (ref "J8") (pin "26") (pinfunction "26_26") (pintype "passive"))
      (node (ref "J8") (pin "28") (pinfunction "28_28") (pintype "passive"))
      (node (ref "J8") (pin "30") (pinfunction "30_30") (pintype "passive"))
      (node (ref "J8") (pin "32") (pinfunction "32_32") (pintype "passive"))
      (node (ref "J8") (pin "34") (pinfunction "34_34") (pintype "passive"))
      (node (ref "J8") (pin "36") (pinfunction "36_36") (pintype "passive"))
      (node (ref "J8") (pin "37") (pinfunction "37_37") (pintype "passive"))
      (node (ref "J8") (pin "38") (pinfunction "38_38") (pintype "passive"))
      (node (ref "J9") (pin "14") (pinfunction "14_14") (pintype "passive"))
      (node (ref "J9") (pin "16") (pinfunction "16_16") (pintype "passive"))
      (node (ref "J9") (pin "18") (pinfunction "18_18") (pintype "passive"))
      (node (ref "J9") (pin "20") (pinfunction "20_20") (pintype "passive"))
      (node (ref "J9") (pin "22") (pinfunction "22_22") (pintype "passive"))
      (node (ref "J9") (pin "24") (pinfunction "24_24") (pintype "passive"))
      (node (ref "J9") (pin "26") (pinfunction "26_26") (pintype "passive"))
      (node (ref "J9") (pin "28") (pinfunction "28_28") (pintype "passive"))
      (node (ref "J9") (pin "30") (pinfunction "30_30") (pintype "passive"))
      (node (ref "J9") (pin "32") (pinfunction "32_32") (pintype "passive"))
      (node (ref "J9") (pin "34") (pinfunction "34_34") (pintype "passive"))
      (node (ref "J9") (pin "36") (pinfunction "36_36") (pintype "passive"))
      (node (ref "J9") (pin "37") (pinfunction "37_37") (pintype "passive"))
      (node (ref "J9") (pin "38") (pinfunction "38_38") (pintype "passive"))
    )
    (net (code "10") (name "Net-(U$1-+)") (class "Default")
      (node (ref "R1") (pin "2") (pinfunction "2_2") (pintype "passive"))
      (node (ref "U$1") (pin "P$4") (pinfunction "+_P$4") (pintype "bidirectional"))
    )
    (net (code "11") (name "Net-(U$1-NO2)") (class "Default")
      (node (ref "K1") (pin "1") (pinfunction "1_1") (pintype "passive"))
      (node (ref "K3") (pin "1") (pinfunction "1_1") (pintype "passive"))
      (node (ref "R1") (pin "1") (pinfunction "1_1") (pintype "passive"))
      (node (ref "U$1") (pin "P$3") (pinfunction "NO2_P$3") (pintype "bidirectional"))
    )
    (net (code "12") (name "START") (class "Default")
      (node (ref "J1") (pin "31") (pinfunction "31_31") (pintype "passive"))
      (node (ref "J10") (pin "31") (pinfunction "31_31") (pintype "passive"))
      (node (ref "J14") (pin "1") (pinfunction "1_1") (pintype "passive"))
      (node (ref "J2") (pin "31") (pinfunction "31_31") (pintype "passive"))
      (node (ref "J3") (pin "31") (pinfunction "31_31") (pintype "passive"))
      (node (ref "J4") (pin "31") (pinfunction "31_31") (pintype "passive"))
      (node (ref "J5") (pin "31") (pinfunction "31_31") (pintype "passive"))
      (node (ref "J6") (pin "31") (pinfunction "31_31") (pintype "passive"))
      (node (ref "J7") (pin "31") (pinfunction "31_31") (pintype "passive"))
      (node (ref "J8") (pin "31") (pinfunction "31_31") (pintype "passive"))
      (node (ref "J9") (pin "31") (pinfunction "31_31") (pintype "passive"))
    )
    (net (code "13") (name "URX") (class "Default")
      (node (ref "J1") (pin "33") (pinfunction "33_33") (pintype "passive"))
      (node (ref "J10") (pin "33") (pinfunction "33_33") (pintype "passive"))
      (node (ref "J19") (pin "1") (pinfunction "1_1") (pintype "passive"))
      (node (ref "J2") (pin "33") (pinfunction "33_33") (pintype "passive"))
      (node (ref "J3") (pin "33") (pinfunction "33_33") (pintype "passive"))
      (node (ref "J4") (pin "33") (pinfunction "33_33") (pintype "passive"))
      (node (ref "J5") (pin "33") (pinfunction "33_33") (pintype "passive"))
      (node (ref "J6") (pin "33") (pinfunction "33_33") (pintype "passive"))
      (node (ref "J7") (pin "33") (pinfunction "33_33") (pintype "passive"))
      (node (ref "J8") (pin "33") (pinfunction "33_33") (pintype "passive"))
      (node (ref "J9") (pin "33") (pinfunction "33_33") (pintype "passive"))
    )
    (net (code "14") (name "UTX") (class "Default")
      (node (ref "J1") (pin "29") (pinfunction "29_29") (pintype "passive"))
      (node (ref "J10") (pin "29") (pinfunction "29_29") (pintype "passive"))
      (node (ref "J11") (pin "1") (pinfunction "1_1") (pintype "passive"))
      (node (ref "J2") (pin "29") (pinfunction "29_29") (pintype "passive"))
      (node (ref "J3") (pin "29") (pinfunction "29_29") (pintype "passive"))
      (node (ref "J4") (pin "29") (pinfunction "29_29") (pintype "passive"))
      (node (ref "J5") (pin "29") (pinfunction "29_29") (pintype "passive"))
      (node (ref "J6") (pin "29") (pinfunction "29_29") (pintype "passive"))
      (node (ref "J7") (pin "29") (pinfunction "29_29") (pintype "passive"))
      (node (ref "J8") (pin "29") (pinfunction "29_29") (pintype "passive"))
      (node (ref "J9") (pin "29") (pinfunction "29_29") (pintype "passive"))
    )
    (net (code "15") (name "unconnected-(J1-Pad1)") (class "Default")
      (node (ref "J1") (pin "1") (pinfunction "1_1") (pintype "passive"))
    )
    (net (code "16") (name "unconnected-(J1-Pad2)") (class "Default")
      (node (ref "J1") (pin "2") (pinfunction "2_2") (pintype "passive"))
    )
    (net (code "17") (name "unconnected-(J1-Pad3)") (class "Default")
      (node (ref "J1") (pin "3") (pinfunction "3_3") (pintype "passive"))
    )
    (net (code "18") (name "unconnected-(J1-Pad4)") (class "Default")
      (node (ref "J1") (pin "4") (pinfunction "4_4") (pintype "passive"))
    )
    (net (code "19") (name "unconnected-(J1-Pad13)") (class "Default")
      (node (ref "J1") (pin "13") (pinfunction "13_13") (pintype "passive"))
    )
    (net (code "20") (name "unconnected-(J1-Pad15)") (class "Default")
      (node (ref "J1") (pin "15") (pinfunction "15_15") (pintype "passive"))
    )
    (net (code "21") (name "unconnected-(J1-Pad17)") (class "Default")
      (node (ref "J1") (pin "17") (pinfunction "17_17") (pintype "passive"))
    )
    (net (code "22") (name "unconnected-(J1-Pad19)") (class "Default")
      (node (ref "J1") (pin "19") (pinfunction "19_19") (pintype "passive"))
    )
    (net (code "23") (name "unconnected-(J1-Pad21)") (class "Default")
      (node (ref "J1") (pin "21") (pinfunction "21_21") (pintype "passive"))
    )
    (net (code "24") (name "unconnected-(J1-Pad23)") (class "Default")
      (node (ref "J1") (pin "23") (pinfunction "23_23") (pintype "passive"))
    )
    (net (code "25") (name "unconnected-(J1-Pad25)") (class "Default")
      (node (ref "J1") (pin "25") (pinfunction "25_25") (pintype "passive"))
    )
    (net (code "26") (name "unconnected-(J1-Pad27)") (class "Default")
      (node (ref "J1") (pin "27") (pinfunction "27_27") (pintype "passive"))
    )
    (net (code "27") (name "unconnected-(J2-Pad1)") (class "Default")
      (node (ref "J2") (pin "1") (pinfunction "1_1") (pintype "passive"))
    )
    (net (code "28") (name "unconnected-(J2-Pad2)") (class "Default")
      (node (ref "J2") (pin "2") (pinfunction "2_2") (pintype "passive"))
    )
    (net (code "29") (name "unconnected-(J2-Pad3)") (class "Default")
      (node (ref "J2") (pin "3") (pinfunction "3_3") (pintype "passive"))
    )
    (net (code "30") (name "unconnected-(J2-Pad4)") (class "Default")
      (node (ref "J2") (pin "4") (pinfunction "4_4") (pintype "passive"))
    )
    (net (code "31") (name "unconnected-(J2-Pad13)") (class "Default")
      (node (ref "J2") (pin "13") (pinfunction "13_13") (pintype "passive"))
    )
    (net (code "32") (name "unconnected-(J2-Pad15)") (class "Default")
      (node (ref "J2") (pin "15") (pinfunction "15_15") (pintype "passive"))
    )
    (net (code "33") (name "unconnected-(J2-Pad17)") (class "Default")
      (node (ref "J2") (pin "17") (pinfunction "17_17") (pintype "passive"))
    )
    (net (code "34") (name "unconnected-(J2-Pad19)") (class "Default")
      (node (ref "J2") (pin "19") (pinfunction "19_19") (pintype "passive"))
    )
    (net (code "35") (name "unconnected-(J2-Pad21)") (class "Default")
      (node (ref "J2") (pin "21") (pinfunction "21_21") (pintype "passive"))
    )
    (net (code "36") (name "unconnected-(J2-Pad23)") (class "Default")
      (node (ref "J2") (pin "23") (pinfunction "23_23") (pintype "passive"))
    )
    (net (code "37") (name "unconnected-(J2-Pad25)") (class "Default")
      (node (ref "J2") (pin "25") (pinfunction "25_25") (pintype "passive"))
    )
    (net (code "38") (name "unconnected-(J2-Pad27)") (class "Default")
      (node (ref "J2") (pin "27") (pinfunction "27_27") (pintype "passive"))
    )
    (net (code "39") (name "unconnected-(J3-Pad1)") (class "Default")
      (node (ref "J3") (pin "1") (pinfunction "1_1") (pintype "passive"))
    )
    (net (code "40") (name "unconnected-(J3-Pad2)") (class "Default")
      (node (ref "J3") (pin "2") (pinfunction "2_2") (pintype "passive"))
    )
    (net (code "41") (name "unconnected-(J3-Pad3)") (class "Default")
      (node (ref "J3") (pin "3") (pinfunction "3_3") (pintype "passive"))
    )
    (net (code "42") (name "unconnected-(J3-Pad4)") (class "Default")
      (node (ref "J3") (pin "4") (pinfunction "4_4") (pintype "passive"))
    )
    (net (code "43") (name "unconnected-(J3-Pad13)") (class "Default")
      (node (ref "J3") (pin "13") (pinfunction "13_13") (pintype "passive"))
    )
    (net (code "44") (name "unconnected-(J3-Pad15)") (class "Default")
      (node (ref "J3") (pin "15") (pinfunction "15_15") (pintype "passive"))
    )
    (net (code "45") (name "unconnected-(J3-Pad17)") (class "Default")
      (node (ref "J3") (pin "17") (pinfunction "17_17") (pintype "passive"))
    )
    (net (code "46") (name "unconnected-(J3-Pad19)") (class "Default")
      (node (ref "J3") (pin "19") (pinfunction "19_19") (pintype "passive"))
    )
    (net (code "47") (name "unconnected-(J3-Pad21)") (class "Default")
      (node (ref "J3") (pin "21") (pinfunction "21_21") (pintype "passive"))
    )
    (net (code "48") (name "unconnected-(J3-Pad23)") (class "Default")
      (node (ref "J3") (pin "23") (pinfunction "23_23") (pintype "passive"))
    )
    (net (code "49") (name "unconnected-(J3-Pad25)") (class "Default")
      (node (ref "J3") (pin "25") (pinfunction "25_25") (pintype "passive"))
    )
    (net (code "50") (name "unconnected-(J3-Pad27)") (class "Default")
      (node (ref "J3") (pin "27") (pinfunction "27_27") (pintype "passive"))
    )
    (net (code "51") (name "unconnected-(J4-Pad1)") (class "Default")
      (node (ref "J4") (pin "1") (pinfunction "1_1") (pintype "passive"))
    )
    (net (code "52") (name "unconnected-(J4-Pad2)") (class "Default")
      (node (ref "J4") (pin "2") (pinfunction "2_2") (pintype "passive"))
    )
    (net (code "53") (name "unconnected-(J4-Pad3)") (class "Default")
      (node (ref "J4") (pin "3") (pinfunction "3_3") (pintype "passive"))
    )
    (net (code "54") (name "unconnected-(J4-Pad4)") (class "Default")
      (node (ref "J4") (pin "4") (pinfunction "4_4") (pintype "passive"))
    )
    (net (code "55") (name "unconnected-(J4-Pad13)") (class "Default")
      (node (ref "J4") (pin "13") (pinfunction "13_13") (pintype "passive"))
    )
    (net (code "56") (name "unconnected-(J4-Pad15)") (class "Default")
      (node (ref "J4") (pin "15") (pinfunction "15_15") (pintype "passive"))
    )
    (net (code "57") (name "unconnected-(J4-Pad17)") (class "Default")
      (node (ref "J4") (pin "17") (pinfunction "17_17") (pintype "passive"))
    )
    (net (code "58") (name "unconnected-(J4-Pad19)") (class "Default")
      (node (ref "J4") (pin "19") (pinfunction "19_19") (pintype "passive"))
    )
    (net (code "59") (name "unconnected-(J4-Pad21)") (class "Default")
      (node (ref "J4") (pin "21") (pinfunction "21_21") (pintype "passive"))
    )
    (net (code "60") (name "unconnected-(J4-Pad23)") (class "Default")
      (node (ref "J4") (pin "23") (pinfunction "23_23") (pintype "passive"))
    )
    (net (code "61") (name "unconnected-(J4-Pad25)") (class "Default")
      (node (ref "J4") (pin "25") (pinfunction "25_25") (pintype "passive"))
    )
    (net (code "62") (name "unconnected-(J4-Pad27)") (class "Default")
      (node (ref "J4") (pin "27") (pinfunction "27_27") (pintype "passive"))
    )
    (net (code "63") (name "unconnected-(J5-Pad1)") (class "Default")
      (node (ref "J5") (pin "1") (pinfunction "1_1") (pintype "passive"))
    )
    (net (code "64") (name "unconnected-(J5-Pad2)") (class "Default")
      (node (ref "J5") (pin "2") (pinfunction "2_2") (pintype "passive"))
    )
    (net (code "65") (name "unconnected-(J5-Pad3)") (class "Default")
      (node (ref "J5") (pin "3") (pinfunction "3_3") (pintype "passive"))
    )
    (net (code "66") (name "unconnected-(J5-Pad4)") (class "Default")
      (node (ref "J5") (pin "4") (pinfunction "4_4") (pintype "passive"))
    )
    (net (code "67") (name "unconnected-(J5-Pad13)") (class "Default")
      (node (ref "J5") (pin "13") (pinfunction "13_13") (pintype "passive"))
    )
    (net (code "68") (name "unconnected-(J5-Pad15)") (class "Default")
      (node (ref "J5") (pin "15") (pinfunction "15_15") (pintype "passive"))
    )
    (net (code "69") (name "unconnected-(J5-Pad17)") (class "Default")
      (node (ref "J5") (pin "17") (pinfunction "17_17") (pintype "passive"))
    )
    (net (code "70") (name "unconnected-(J5-Pad19)") (class "Default")
      (node (ref "J5") (pin "19") (pinfunction "19_19") (pintype "passive"))
    )
    (net (code "71") (name "unconnected-(J5-Pad21)") (class "Default")
      (node (ref "J5") (pin "21") (pinfunction "21_21") (pintype "passive"))
    )
    (net (code "72") (name "unconnected-(J5-Pad23)") (class "Default")
      (node (ref "J5") (pin "23") (pinfunction "23_23") (pintype "passive"))
    )
    (net (code "73") (name "unconnected-(J5-Pad25)") (class "Default")
      (node (ref "J5") (pin "25") (pinfunction "25_25") (pintype "passive"))
    )
    (net (code "74") (name "unconnected-(J5-Pad27)") (class "Default")
      (node (ref "J5") (pin "27") (pinfunction "27_27") (pintype "passive"))
    )
    (net (code "75") (name "unconnected-(J6-Pad1)") (class "Default")
      (node (ref "J6") (pin "1") (pinfunction "1_1") (pintype "passive"))
    )
    (net (code "76") (name "unconnected-(J6-Pad2)") (class "Default")
      (node (ref "J6") (pin "2") (pinfunction "2_2") (pintype "passive"))
    )
    (net (code "77") (name "unconnected-(J6-Pad3)") (class "Default")
      (node (ref "J6") (pin "3") (pinfunction "3_3") (pintype "passive"))
    )
    (net (code "78") (name "unconnected-(J6-Pad4)") (class "Default")
      (node (ref "J6") (pin "4") (pinfunction "4_4") (pintype "passive"))
    )
    (net (code "79") (name "unconnected-(J6-Pad13)") (class "Default")
      (node (ref "J6") (pin "13") (pinfunction "13_13") (pintype "passive"))
    )
    (net (code "80") (name "unconnected-(J6-Pad15)") (class "Default")
      (node (ref "J6") (pin "15") (pinfunction "15_15") (pintype "passive"))
    )
    (net (code "81") (name "unconnected-(J6-Pad17)") (class "Default")
      (node (ref "J6") (pin "17") (pinfunction "17_17") (pintype "passive"))
    )
    (net (code "82") (name "unconnected-(J6-Pad19)") (class "Default")
      (node (ref "J6") (pin "19") (pinfunction "19_19") (pintype "passive"))
    )
    (net (code "83") (name "unconnected-(J6-Pad21)") (class "Default")
      (node (ref "J6") (pin "21") (pinfunction "21_21") (pintype "passive"))
    )
    (net (code "84") (name "unconnected-(J6-Pad23)") (class "Default")
      (node (ref "J6") (pin "23") (pinfunction "23_23") (pintype "passive"))
    )
    (net (code "85") (name "unconnected-(J6-Pad25)") (class "Default")
      (node (ref "J6") (pin "25") (pinfunction "25_25") (pintype "passive"))
    )
    (net (code "86") (name "unconnected-(J6-Pad27)") (class "Default")
      (node (ref "J6") (pin "27") (pinfunction "27_27") (pintype "passive"))
    )
    (net (code "87") (name "unconnected-(J7-Pad1)") (class "Default")
      (node (ref "J7") (pin "1") (pinfunction "1_1") (pintype "passive"))
    )
    (net (code "88") (name "unconnected-(J7-Pad2)") (class "Default")
      (node (ref "J7") (pin "2") (pinfunction "2_2") (pintype "passive"))
    )
    (net (code "89") (name "unconnected-(J7-Pad3)") (class "Default")
      (node (ref "J7") (pin "3") (pinfunction "3_3") (pintype "passive"))
    )
    (net (code "90") (name "unconnected-(J7-Pad4)") (class "Default")
      (node (ref "J7") (pin "4") (pinfunction "4_4") (pintype "passive"))
    )
    (net (code "91") (name "unconnected-(J7-Pad13)") (class "Default")
      (node (ref "J7") (pin "13") (pinfunction "13_13") (pintype "passive"))
    )
    (net (code "92") (name "unconnected-(J7-Pad15)") (class "Default")
      (node (ref "J7") (pin "15") (pinfunction "15_15") (pintype "passive"))
    )
    (net (code "93") (name "unconnected-(J7-Pad17)") (class "Default")
      (node (ref "J7") (pin "17") (pinfunction "17_17") (pintype "passive"))
    )
    (net (code "94") (name "unconnected-(J7-Pad19)") (class "Default")
      (node (ref "J7") (pin "19") (pinfunction "19_19") (pintype "passive"))
    )
    (net (code "95") (name "unconnected-(J7-Pad21)") (class "Default")
      (node (ref "J7") (pin "21") (pinfunction "21_21") (pintype "passive"))
    )
    (net (code "96") (name "unconnected-(J7-Pad23)") (class "Default")
      (node (ref "J7") (pin "23") (pinfunction "23_23") (pintype "passive"))
    )
    (net (code "97") (name "unconnected-(J7-Pad25)") (class "Default")
      (node (ref "J7") (pin "25") (pinfunction "25_25") (pintype "passive"))
    )
    (net (code "98") (name "unconnected-(J7-Pad27)") (class "Default")
      (node (ref "J7") (pin "27") (pinfunction "27_27") (pintype "passive"))
    )
    (net (code "99") (name "unconnected-(J8-Pad1)") (class "Default")
      (node (ref "J8") (pin "1") (pinfunction "1_1") (pintype "passive"))
    )
    (net (code "100") (name "unconnected-(J8-Pad2)") (class "Default")
      (node (ref "J8") (pin "2") (pinfunction "2_2") (pintype "passive"))
    )
    (net (code "101") (name "unconnected-(J8-Pad3)") (class "Default")
      (node (ref "J8") (pin "3") (pinfunction "3_3") (pintype "passive"))
    )
    (net (code "102") (name "unconnected-(J8-Pad4)") (class "Default")
      (node (ref "J8") (pin "4") (pinfunction "4_4") (pintype "passive"))
    )
    (net (code "103") (name "unconnected-(J8-Pad13)") (class "Default")
      (node (ref "J8") (pin "13") (pinfunction "13_13") (pintype "passive"))
    )
    (net (code "104") (name "unconnected-(J8-Pad15)") (class "Default")
      (node (ref "J8") (pin "15") (pinfunction "15_15") (pintype "passive"))
    )
    (net (code "105") (name "unconnected-(J8-Pad17)") (class "Default")
      (node (ref "J8") (pin "17") (pinfunction "17_17") (pintype "passive"))
    )
    (net (code "106") (name "unconnected-(J8-Pad19)") (class "Default")
      (node (ref "J8") (pin "19") (pinfunction "19_19") (pintype "passive"))
    )
    (net (code "107") (name "unconnected-(J8-Pad21)") (class "Default")
      (node (ref "J8") (pin "21") (pinfunction "21_21") (pintype "passive"))
    )
    (net (code "108") (name "unconnected-(J8-Pad23)") (class "Default")
      (node (ref "J8") (pin "23") (pinfunction "23_23") (pintype "passive"))
    )
    (net (code "109") (name "unconnected-(J8-Pad25)") (class "Default")
      (node (ref "J8") (pin "25") (pinfunction "25_25") (pintype "passive"))
    )
    (net (code "110") (name "unconnected-(J8-Pad27)") (class "Default")
      (node (ref "J8") (pin "27") (pinfunction "27_27") (pintype "passive"))
    )
    (net (code "111") (name "unconnected-(J9-Pad1)") (class "Default")
      (node (ref "J9") (pin "1") (pinfunction "1_1") (pintype "passive"))
    )
    (net (code "112") (name "unconnected-(J9-Pad2)") (class "Default")
      (node (ref "J9") (pin "2") (pinfunction "2_2") (pintype "passive"))
    )
    (net (code "113") (name "unconnected-(J9-Pad3)") (class "Default")
      (node (ref "J9") (pin "3") (pinfunction "3_3") (pintype "passive"))
    )
    (net (code "114") (name "unconnected-(J9-Pad4)") (class "Default")
      (node (ref "J9") (pin "4") (pinfunction "4_4") (pintype "passive"))
    )
    (net (code "115") (name "unconnected-(J9-Pad13)") (class "Default")
      (node (ref "J9") (pin "13") (pinfunction "13_13") (pintype "passive"))
    )
    (net (code "116") (name "unconnected-(J9-Pad15)") (class "Default")
      (node (ref "J9") (pin "15") (pinfunction "15_15") (pintype "passive"))
    )
    (net (code "117") (name "unconnected-(J9-Pad17)") (class "Default")
      (node (ref "J9") (pin "17") (pinfunction "17_17") (pintype "passive"))
    )
    (net (code "118") (name "unconnected-(J9-Pad19)") (class "Default")
      (node (ref "J9") (pin "19") (pinfunction "19_19") (pintype "passive"))
    )
    (net (code "119") (name "unconnected-(J9-Pad21)") (class "Default")
      (node (ref "J9") (pin "21") (pinfunction "21_21") (pintype "passive"))
    )
    (net (code "120") (name "unconnected-(J9-Pad23)") (class "Default")
      (node (ref "J9") (pin "23") (pinfunction "23_23") (pintype "passive"))
    )
    (net (code "121") (name "unconnected-(J9-Pad25)") (class "Default")
      (node (ref "J9") (pin "25") (pinfunction "25_25") (pintype "passive"))
    )
    (net (code "122") (name "unconnected-(J9-Pad27)") (class "Default")
      (node (ref "J9") (pin "27") (pinfunction "27_27") (pintype "passive"))
    )
    (net (code "123") (name "unconnected-(J10-Pad1)") (class "Default")
      (node (ref "J10") (pin "1") (pinfunction "1_1") (pintype "passive"))
    )
    (net (code "124") (name "unconnected-(J10-Pad2)") (class "Default")
      (node (ref "J10") (pin "2") (pinfunction "2_2") (pintype "passive"))
    )
    (net (code "125") (name "unconnected-(J10-Pad3)") (class "Default")
      (node (ref "J10") (pin "3") (pinfunction "3_3") (pintype "passive"))
    )
    (net (code "126") (name "unconnected-(J10-Pad4)") (class "Default")
      (node (ref "J10") (pin "4") (pinfunction "4_4") (pintype "passive"))
    )
    (net (code "127") (name "unconnected-(J10-Pad13)") (class "Default")
      (node (ref "J10") (pin "13") (pinfunction "13_13") (pintype "passive"))
    )
    (net (code "128") (name "unconnected-(J10-Pad15)") (class "Default")
      (node (ref "J10") (pin "15") (pinfunction "15_15") (pintype "passive"))
    )
    (net (code "129") (name "unconnected-(J10-Pad17)") (class "Default")
      (node (ref "J10") (pin "17") (pinfunction "17_17") (pintype "passive"))
    )
    (net (code "130") (name "unconnected-(J10-Pad19)") (class "Default")
      (node (ref "J10") (pin "19") (pinfunction "19_19") (pintype "passive"))
    )
    (net (code "131") (name "unconnected-(J10-Pad21)") (class "Default")
      (node (ref "J10") (pin "21") (pinfunction "21_21") (pintype "passive"))
    )
    (net (code "132") (name "unconnected-(J10-Pad23)") (class "Default")
      (node (ref "J10") (pin "23") (pinfunction "23_23") (pintype "passive"))
    )
    (net (code "133") (name "unconnected-(J10-Pad25)") (class "Default")
      (node (ref "J10") (pin "25") (pinfunction "25_25") (pintype "passive"))
    )
    (net (code "134") (name "unconnected-(J10-Pad27)") (class "Default")
      (node (ref "J10") (pin "27") (pinfunction "27_27") (pintype "passive"))
    )
    (net (code "135") (name "unconnected-(K1-2-Pad3)") (class "Default")
      (node (ref "K1") (pin "3") (pinfunction "2_3") (pintype "passive"))
    )
    (net (code "136") (name "unconnected-(K1-7-Pad10)") (class "Default")
      (node (ref "K1") (pin "10") (pinfunction "7_10") (pintype "passive"))
    )
    (net (code "137") (name "unconnected-(K3-2-Pad3)") (class "Default")
      (node (ref "K3") (pin "3") (pinfunction "2_3") (pintype "passive"))
    )
    (net (code "138") (name "unconnected-(K3-5-Pad8)") (class "Default")
      (node (ref "K3") (pin "8") (pinfunction "5_8") (pintype "passive"))
    )
    (net (code "139") (name "unconnected-(K3-6-Pad9)") (class "Default")
      (node (ref "K3") (pin "9") (pinfunction "6_9") (pintype "passive"))
    )
    (net (code "140") (name "unconnected-(K3-7-Pad10)") (class "Default")
      (node (ref "K3") (pin "10") (pinfunction "7_10") (pintype "passive"))
    )
  )
)
